# module_mq2.net
KiCad netlist of a schematic drawn in EAGLE
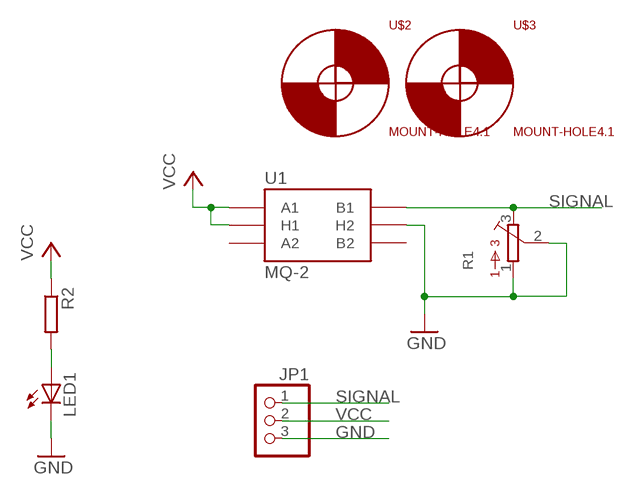
[diagram p0: schematic, sheet 1]

(export (version "E")
  (design (tool "Eeschema 10.0.6"))
  (components
    (comp (ref "JP1")
      (value "PINHD-1X3")
      (footprint "eagle-import:1X03")
      (libsource (lib "eagle-import") (part "PINHD-1X3"))
    )
    (comp (ref "LED1")
      (value "LED5MM")
      (footprint "eagle-import:LED5MM")
      (libsource (lib "eagle-import") (part "LED5MM"))
    )
    (comp (ref "R1")
      (value "3386-P")
      (footprint "eagle-import:3386P")
      (libsource (lib "eagle-import") (part "3386-P"))
    )
    (comp (ref "R2")
      (value "R-EU_0207_7")
      (footprint "eagle-import:0207_7")
      (libsource (lib "eagle-import") (part "R-EU_0207_7"))
    )
    (comp (ref "U$2")
      (value "MOUNT-HOLE4.1")
      (footprint "eagle-import:4.1")
      (libsource (lib "eagle-import") (part "MOUNT-HOLE4.1"))
    )
    (comp (ref "U$3")
      (value "MOUNT-HOLE4.1")
      (footprint "eagle-import:4.1")
      (libsource (lib "eagle-import") (part "MOUNT-HOLE4.1"))
    )
    (comp (ref "U1")
      (value "MQ-2")
      (footprint "eagle-import:MQ-2")
      (libsource (lib "eagle-import") (part "MQ-2"))
    )
  )
  (nets
    (net (code "1") (name "/SIGNAL") (class "Default")
      (node (ref "JP1") (pin "1") (pinfunction "1_1") (pintype "passive"))
      (node (ref "R1") (pin "3") (pinfunction "3_3") (pintype "passive"))
      (node (ref "U1") (pin "B1") (pinfunction "B1_B1") (pintype "bidirectional"))
    )
    (net (code "2") (name "GND") (class "Default")
      (node (ref "JP1") (pin "3") (pinfunction "3_3") (pintype "passive"))
      (node (ref "LED1") (pin "K") (pinfunction "C_K") (pintype "passive"))
      (node (ref "R1") (pin "1") (pinfunction "1_1") (pintype "passive"))
      (node (ref "R1") (pin "2") (pinfunction "2_2") (pintype "passive"))
      (node (ref "U1") (pin "HB") (pinfunction "H2_HB") (pintype "bidirectional"))
    )
    (net (code "3") (name "Net-(LED1-PadA)") (class "Default")
      (node (ref "LED1") (pin "A") (pinfunction "A_A") (pintype "passive"))
      (node (ref "R2") (pin "2") (pinfunction "2_2") (pintype "passive"))
    )
    (net (code "4") (name "VCC") (class "Default")
      (node (ref "JP1") (pin "2") (pinfunction "2_2") (pintype "passive"))
      (node (ref "R2") (pin "1") (pinfunction "1_1") (pintype "passive"))
      (node (ref "U1") (pin "A1") (pinfunction "A1_A1") (pintype "bidirectional"))
      (node (ref "U1") (pin "HA") (pinfunction "H1_HA") (pintype "bidirectional"))
    )
    (net (code "5") (name "unconnected-(U1-PadA2)") (class "Default")
      (node (ref "U1") (pin "A2") (pinfunction "A2_A2") (pintype "bidirectional"))
    )
    (net (code "6") (name "unconnected-(U1-PadB2)") (class "Default")
      (node (ref "U1") (pin "B2") (pinfunction "B2_B2") (pintype "bidirectional"))
    )
  )
)
